# USB.net
KiCad netlist of a schematic drawn in Altium Designer
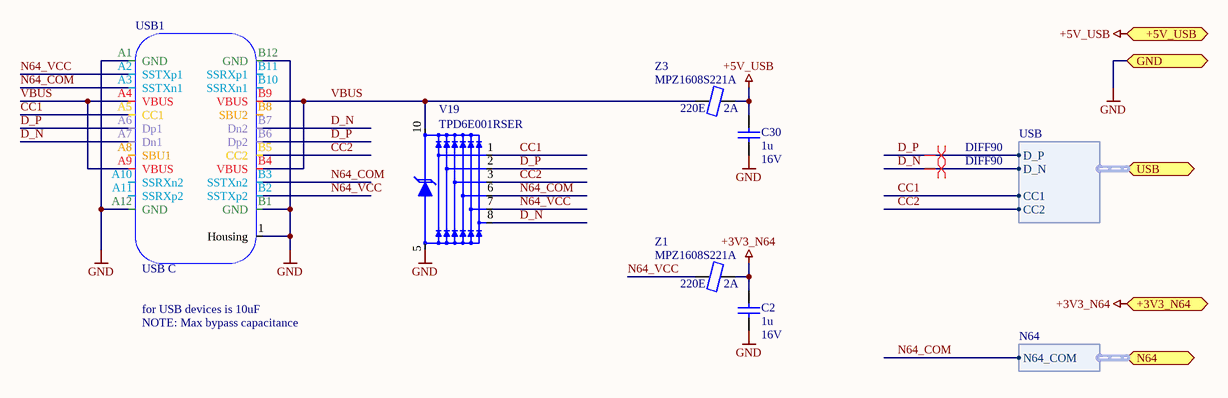
[diagram p0: USB.SchDoc]

(export (version "E")
  (design (tool "Eeschema 10.0.6"))
  (components
    (comp (ref "C2")
      (value "1u")
      (footprint "SMD_CAP_0603")
      (description "1µF ±10% 16V Ceramic Capacitor X7R 0603 (1608 Metric)")
      (fields (field (name "VALUE2") "16V") (field (name "Comment") "C_SMD_CER_1U_16V_10%_X7R_0603"))
      (libsource (lib "AM") (part "C_SMD_CER_1U_16V_10%_X7R_0603"))
    )
    (comp (ref "C30")
      (value "1u")
      (footprint "SMD_CAP_0603")
      (description "1µF ±10% 16V Ceramic Capacitor X7R 0603 (1608 Metric)")
      (fields (field (name "VALUE2") "16V") (field (name "Comment") "C_SMD_CER_1U_16V_10%_X7R_0603"))
      (libsource (lib "AM") (part "C_SMD_CER_1U_16V_10%_X7R_0603"))
    )
    (comp (ref "USB1")
      (value "*")
      (footprint "SMD_CON_USB_TYPEC_VERTICAL_10132328-10011LF")
      (fields (field (name "TYPE") "USB C"))
      (libsource (lib "AM") (part "X_CONNECTOR_USB_TYPEC_VERTICAL"))
    )
    (comp (ref "V19")
      (value "V_SMD_TVS_TPD6E001RSER_UQFN-10")
      (footprint "SMD_UQFN-10")
      (description "Clamp Ipp Tvs Diode Surface Mount 10-UQFN (2.0x1.5)")
      (fields (field (name "TYPE") "TPD6E001RSER"))
      (libsource (lib "AM") (part "V_SMD_TVS_TPD6E001RSER_UQFN-10"))
    )
    (comp (ref "Z1")
      (value "220E")
      (footprint "SMD_RES_0603")
      (description "Ferrite Beads")
      (fields
        (field (name "TYPE") "MPZ1608S221A")
        (field (name "VALUE2") "2A")
        (field (name "Comment") "Z_SMD_FERRITE_2A_220E@100MHZ_0603")
      )
      (libsource (lib "AM") (part "Z_SMD_FERRITE_2A_220E@100MHZ_0603"))
    )
    (comp (ref "Z3")
      (value "220E")
      (footprint "SMD_RES_0603")
      (description "Ferrite Beads")
      (fields
        (field (name "TYPE") "MPZ1608S221A")
        (field (name "VALUE2") "2A")
        (field (name "Comment") "Z_SMD_FERRITE_2A_220E@100MHZ_0603")
      )
      (libsource (lib "AM") (part "Z_SMD_FERRITE_2A_220E@100MHZ_0603"))
    )
  )
  (nets
    (net (code "3") (name "+3V3_N64") (class "Default")
      (node (ref "C2") (pin "2") (pinfunction "2_2") (pintype "passive"))
      (node (ref "Z1") (pin "2") (pinfunction "2_2") (pintype "passive"))
    )
    (net (code "4") (name "+5V_USB") (class "Default")
      (node (ref "C30") (pin "2") (pinfunction "2_2") (pintype "passive"))
      (node (ref "Z3") (pin "2") (pinfunction "2_2") (pintype "passive"))
    )
    (net (code "5") (name "/CC1") (class "Default")
      (node (ref "USB1") (pin "A5") (pinfunction "CC1_A5") (pintype "passive"))
      (node (ref "V19") (pin "1") (pinfunction "1_1") (pintype "passive"))
    )
    (net (code "6") (name "/CC2") (class "Default")
      (node (ref "USB1") (pin "B5") (pinfunction "CC2_B5") (pintype "passive"))
      (node (ref "V19") (pin "3") (pinfunction "3_3") (pintype "passive"))
    )
    (net (code "7") (name "/D_N") (class "Default")
      (node (ref "USB1") (pin "A7") (pinfunction "Dn1_A7") (pintype "passive"))
      (node (ref "USB1") (pin "B7") (pinfunction "Dn2_B7") (pintype "passive"))
      (node (ref "V19") (pin "8") (pinfunction "8_8") (pintype "passive"))
    )
    (net (code "8") (name "/D_P") (class "Default")
      (node (ref "USB1") (pin "A6") (pinfunction "Dp1_A6") (pintype "passive"))
      (node (ref "USB1") (pin "B6") (pinfunction "Dp2_B6") (pintype "passive"))
      (node (ref "V19") (pin "2") (pinfunction "2_2") (pintype "passive"))
    )
    (net (code "9") (name "/N64_COM") (class "Default")
      (node (ref "USB1") (pin "A3") (pinfunction "SSTXn1_A3") (pintype "passive"))
      (node (ref "USB1") (pin "B3") (pinfunction "SSTXn2_B3") (pintype "passive"))
      (node (ref "V19") (pin "6") (pinfunction "6_6") (pintype "passive"))
    )
    (net (code "10") (name "/N64_VCC") (class "Default")
      (node (ref "USB1") (pin "A2") (pinfunction "SSTXp1_A2") (pintype "passive"))
      (node (ref "USB1") (pin "B2") (pinfunction "SSTXp2_B2") (pintype "passive"))
      (node (ref "V19") (pin "7") (pinfunction "7_7") (pintype "passive"))
      (node (ref "Z1") (pin "1") (pinfunction "1_1") (pintype "passive"))
    )
    (net (code "11") (name "/VBUS") (class "Default")
      (node (ref "USB1") (pin "A4") (pinfunction "VBUS_A4") (pintype "passive"))
      (node (ref "USB1") (pin "A9") (pinfunction "VBUS_A9") (pintype "passive"))
      (node (ref "USB1") (pin "B4") (pinfunction "VBUS_B4") (pintype "passive"))
      (node (ref "USB1") (pin "B9") (pinfunction "VBUS_B9") (pintype "passive"))
      (node (ref "V19") (pin "10") (pinfunction "10_10") (pintype "passive"))
      (node (ref "Z3") (pin "1") (pinfunction "1_1") (pintype "passive"))
    )
    (net (code "14") (name "GND") (class "Default")
      (node (ref "C2") (pin "1") (pinfunction "1_1") (pintype "passive"))
      (node (ref "C30") (pin "1") (pinfunction "1_1") (pintype "passive"))
      (node (ref "USB1") (pin "1") (pinfunction "Housing_1") (pintype "passive"))
      (node (ref "USB1") (pin "A1") (pinfunction "GND_A1") (pintype "passive"))
      (node (ref "USB1") (pin "A12") (pinfunction "GND_A12") (pintype "passive"))
      (node (ref "USB1") (pin "B1") (pinfunction "GND_B1") (pintype "passive"))
      (node (ref "USB1") (pin "B12") (pinfunction "GND_B12") (pintype "passive"))
      (node (ref "V19") (pin "5") (pinfunction "5_5") (pintype "passive"))
    )
    (net (code "15") (name "unconnected-(USB1-SBU1-PadA8)") (class "Default")
      (node (ref "USB1") (pin "A8") (pinfunction "SBU1_A8") (pintype "passive"))
    )
    (net (code "16") (name "unconnected-(USB1-SBU2-PadB8)") (class "Default")
      (node (ref "USB1") (pin "B8") (pinfunction "SBU2_B8") (pintype "passive"))
    )
    (net (code "17") (name "unconnected-(USB1-SSRXn1-PadB10)") (class "Default")
      (node (ref "USB1") (pin "B10") (pinfunction "SSRXn1_B10") (pintype "passive"))
    )
    (net (code "18") (name "unconnected-(USB1-SSRXn2-PadA10)") (class "Default")
      (node (ref "USB1") (pin "A10") (pinfunction "SSRXn2_A10") (pintype "passive"))
    )
    (net (code "19") (name "unconnected-(USB1-SSRXp1-PadB11)") (class "Default")
      (node (ref "USB1") (pin "B11") (pinfunction "SSRXp1_B11") (pintype "passive"))
    )
    (net (code "20") (name "unconnected-(USB1-SSRXp2-PadA11)") (class "Default")
      (node (ref "USB1") (pin "A11") (pinfunction "SSRXp2_A11") (pintype "passive"))
    )
  )
)
